# Downstream_Port.net
KiCad netlist of a schematic drawn in Altium Designer
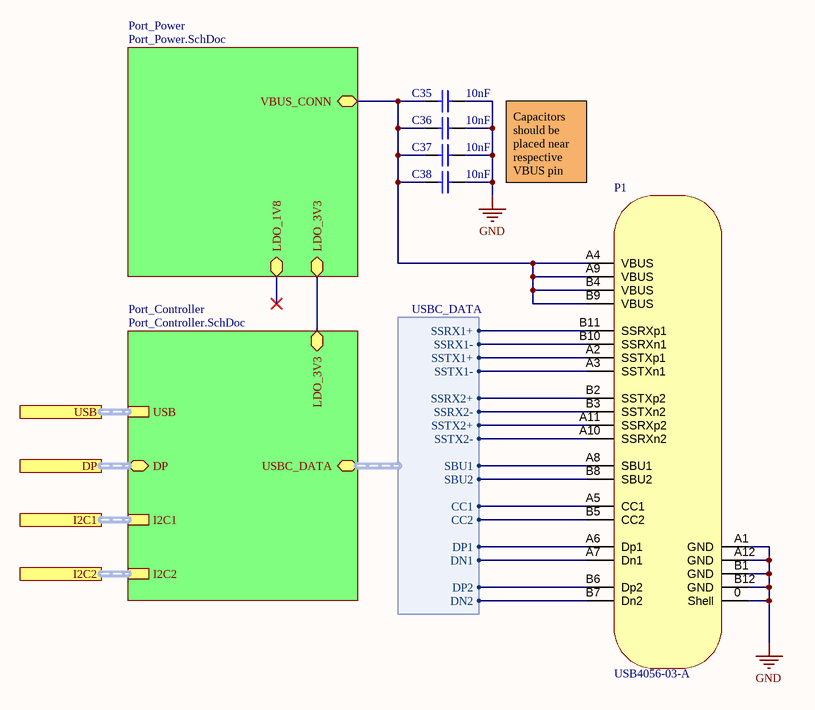
[diagram p0: Downstream_Port.SchDoc]

(export (version "E")
  (design (tool "Eeschema 10.0.6"))
  (components
    (comp (ref "C35")
      (value "10nF")
      (footprint "CAP0402")
      (description "10000 pF ±10% 50V Ceramic Capacitor X7R 0402 (1005 Metric)")
      (fields (field (name "VOLTAGE") "50V") (field (name "Comment") "CC0402KRX7R9BB103"))
      (libsource (lib "Schlib1") (part "CC0402KRX7R9BB103"))
    )
    (comp (ref "C36")
      (value "10nF")
      (footprint "CAP0402")
      (description "10000 pF ±10% 50V Ceramic Capacitor X7R 0402 (1005 Metric)")
      (fields (field (name "VOLTAGE") "50V") (field (name "Comment") "CC0402KRX7R9BB103"))
      (libsource (lib "Schlib1") (part "CC0402KRX7R9BB103"))
    )
    (comp (ref "C37")
      (value "10nF")
      (footprint "CAP0402")
      (description "10000 pF ±10% 50V Ceramic Capacitor X7R 0402 (1005 Metric)")
      (fields (field (name "VOLTAGE") "50V") (field (name "Comment") "CC0402KRX7R9BB103"))
      (libsource (lib "Schlib1") (part "CC0402KRX7R9BB103"))
    )
    (comp (ref "C38")
      (value "10nF")
      (footprint "CAP0402")
      (description "10000 pF ±10% 50V Ceramic Capacitor X7R 0402 (1005 Metric)")
      (fields (field (name "VOLTAGE") "50V") (field (name "Comment") "CC0402KRX7R9BB103"))
      (libsource (lib "Schlib1") (part "CC0402KRX7R9BB103"))
    )
    (comp (ref "P1")
      (value "USB4056-03-A")
      (footprint "USB4056-03-A")
      (fields (field (name "MANUFACTURER") "GCT") (field (name "VOLTAGE") "48VDC"))
      (libsource (lib "Schlib1") (part "USB4056-03-A"))
    )
  )
  (nets
    (net (code "2") (name "/CC1") (class "Default")
      (node (ref "P1") (pin "A5") (pinfunction "CC1_A5") (pintype "passive"))
    )
    (net (code "3") (name "/CC2") (class "Default")
      (node (ref "P1") (pin "B5") (pinfunction "CC2_B5") (pintype "passive"))
    )
    (net (code "4") (name "/DN1") (class "Default")
      (node (ref "P1") (pin "A7") (pinfunction "Dn1_A7") (pintype "passive"))
    )
    (net (code "5") (name "/DN2") (class "Default")
      (node (ref "P1") (pin "B7") (pinfunction "Dn2_B7") (pintype "passive"))
    )
    (net (code "7") (name "/DP1") (class "Default")
      (node (ref "P1") (pin "A6") (pinfunction "Dp1_A6") (pintype "passive"))
    )
    (net (code "8") (name "/DP2") (class "Default")
      (node (ref "P1") (pin "B6") (pinfunction "Dp2_B6") (pintype "passive"))
    )
    (net (code "13") (name "/SBU1") (class "Default")
      (node (ref "P1") (pin "A8") (pinfunction "SBU1_A8") (pintype "passive"))
    )
    (net (code "14") (name "/SBU2") (class "Default")
      (node (ref "P1") (pin "B8") (pinfunction "SBU2_B8") (pintype "passive"))
    )
    (net (code "15") (name "/SSRX1+") (class "Default")
      (node (ref "P1") (pin "B11") (pinfunction "SSRXp1_B11") (pintype "passive"))
    )
    (net (code "16") (name "/SSRX1-") (class "Default")
      (node (ref "P1") (pin "B10") (pinfunction "SSRXn1_B10") (pintype "passive"))
    )
    (net (code "17") (name "/SSRX2+") (class "Default")
      (node (ref "P1") (pin "B2") (pinfunction "SSTXp2_B2") (pintype "passive"))
    )
    (net (code "18") (name "/SSRX2-") (class "Default")
      (node (ref "P1") (pin "B3") (pinfunction "SSTXn2_B3") (pintype "passive"))
    )
    (net (code "19") (name "/SSTX1+") (class "Default")
      (node (ref "P1") (pin "A2") (pinfunction "SSTXp1_A2") (pintype "passive"))
    )
    (net (code "20") (name "/SSTX1-") (class "Default")
      (node (ref "P1") (pin "A3") (pinfunction "SSTXn1_A3") (pintype "passive"))
    )
    (net (code "21") (name "/SSTX2+") (class "Default")
      (node (ref "P1") (pin "A11") (pinfunction "SSRXp2_A11") (pintype "passive"))
    )
    (net (code "22") (name "/SSTX2-") (class "Default")
      (node (ref "P1") (pin "A10") (pinfunction "SSRXn2_A10") (pintype "passive"))
    )
    (net (code "24") (name "/VBUS_CONN") (class "Default")
      (node (ref "C35") (pin "2") (pinfunction "2_2") (pintype "passive"))
      (node (ref "C36") (pin "2") (pinfunction "2_2") (pintype "passive"))
      (node (ref "C37") (pin "2") (pinfunction "2_2") (pintype "passive"))
      (node (ref "C38") (pin "2") (pinfunction "2_2") (pintype "passive"))
      (node (ref "P1") (pin "A4") (pinfunction "VBUS_A4") (pintype "passive"))
      (node (ref "P1") (pin "A9") (pinfunction "VBUS_A9") (pintype "passive"))
      (node (ref "P1") (pin "B4") (pinfunction "VBUS_B4") (pintype "passive"))
      (node (ref "P1") (pin "B9") (pinfunction "VBUS_B9") (pintype "passive"))
    )
    (net (code "26") (name "GND") (class "Default")
      (node (ref "C35") (pin "1") (pinfunction "1_1") (pintype "passive"))
      (node (ref "C36") (pin "1") (pinfunction "1_1") (pintype "passive"))
      (node (ref "C37") (pin "1") (pinfunction "1_1") (pintype "passive"))
      (node (ref "C38") (pin "1") (pinfunction "1_1") (pintype "passive"))
      (node (ref "P1") (pin "0") (pinfunction "Shell_0") (pintype "passive"))
      (node (ref "P1") (pin "A1") (pinfunction "GND_A1") (pintype "passive"))
      (node (ref "P1") (pin "A12") (pinfunction "GND_A12") (pintype "passive"))
      (node (ref "P1") (pin "B1") (pinfunction "GND_B1") (pintype "passive"))
      (node (ref "P1") (pin "B12") (pinfunction "GND_B12") (pintype "passive"))
    )
  )
)
